# Beta22_fettran.net
KiCad netlist of a schematic drawn in EAGLE
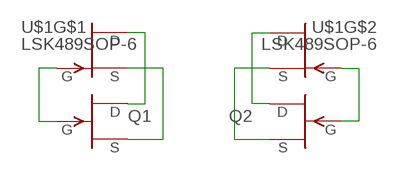
[diagram p0: schematic, sheet 1]

(export (version "E")
  (design (tool "Eeschema 10.0.6"))
  (components
    (comp (ref "Q1")
      (value "2SK170")
      (footprint "eagle-import:TO92-")
      (libsource (lib "eagle-import") (part "2SK170"))
    )
    (comp (ref "Q2")
      (value "2SK170")
      (footprint "eagle-import:TO92-")
      (libsource (lib "eagle-import") (part "2SK170"))
    )
    (comp (ref "U$1")
      (value "LSK489SOP-6")
      (footprint "eagle-import:SOT-23-6")
      (libsource (lib "eagle-import") (part "LSK489SOP-6"))
    )
  )
  (nets
    (net (code "1") (name "Net-(Q1-D)") (class "Default")
      (node (ref "Q1") (pin "1") (pinfunction "D_1") (pintype "passive"))
      (node (ref "U$1") (pin "2") (pinfunction "D_2") (pintype "passive"))
    )
    (net (code "2") (name "Net-(Q1-G)") (class "Default")
      (node (ref "Q1") (pin "2") (pinfunction "G_2") (pintype "passive"))
      (node (ref "U$1") (pin "1") (pinfunction "G_1") (pintype "passive"))
    )
    (net (code "3") (name "Net-(Q1-S)") (class "Default")
      (node (ref "Q1") (pin "3") (pinfunction "S_3") (pintype "passive"))
      (node (ref "U$1") (pin "3") (pinfunction "S_3") (pintype "passive"))
    )
    (net (code "4") (name "Net-(Q2-D)") (class "Default")
      (node (ref "Q2") (pin "1") (pinfunction "D_1") (pintype "passive"))
      (node (ref "U$1") (pin "5") (pinfunction "D_5") (pintype "passive"))
    )
    (net (code "5") (name "Net-(Q2-G)") (class "Default")
      (node (ref "Q2") (pin "2") (pinfunction "G_2") (pintype "passive"))
      (node (ref "U$1") (pin "4") (pinfunction "G_4") (pintype "passive"))
    )
    (net (code "6") (name "Net-(Q2-S)") (class "Default")
      (node (ref "Q2") (pin "3") (pinfunction "S_3") (pintype "passive"))
      (node (ref "U$1") (pin "6") (pinfunction "S_6") (pintype "passive"))
    )
  )
)
